# SCH_Hunter_2024-12-30.net
KiCad netlist of a schematic drawn in EasyEDA
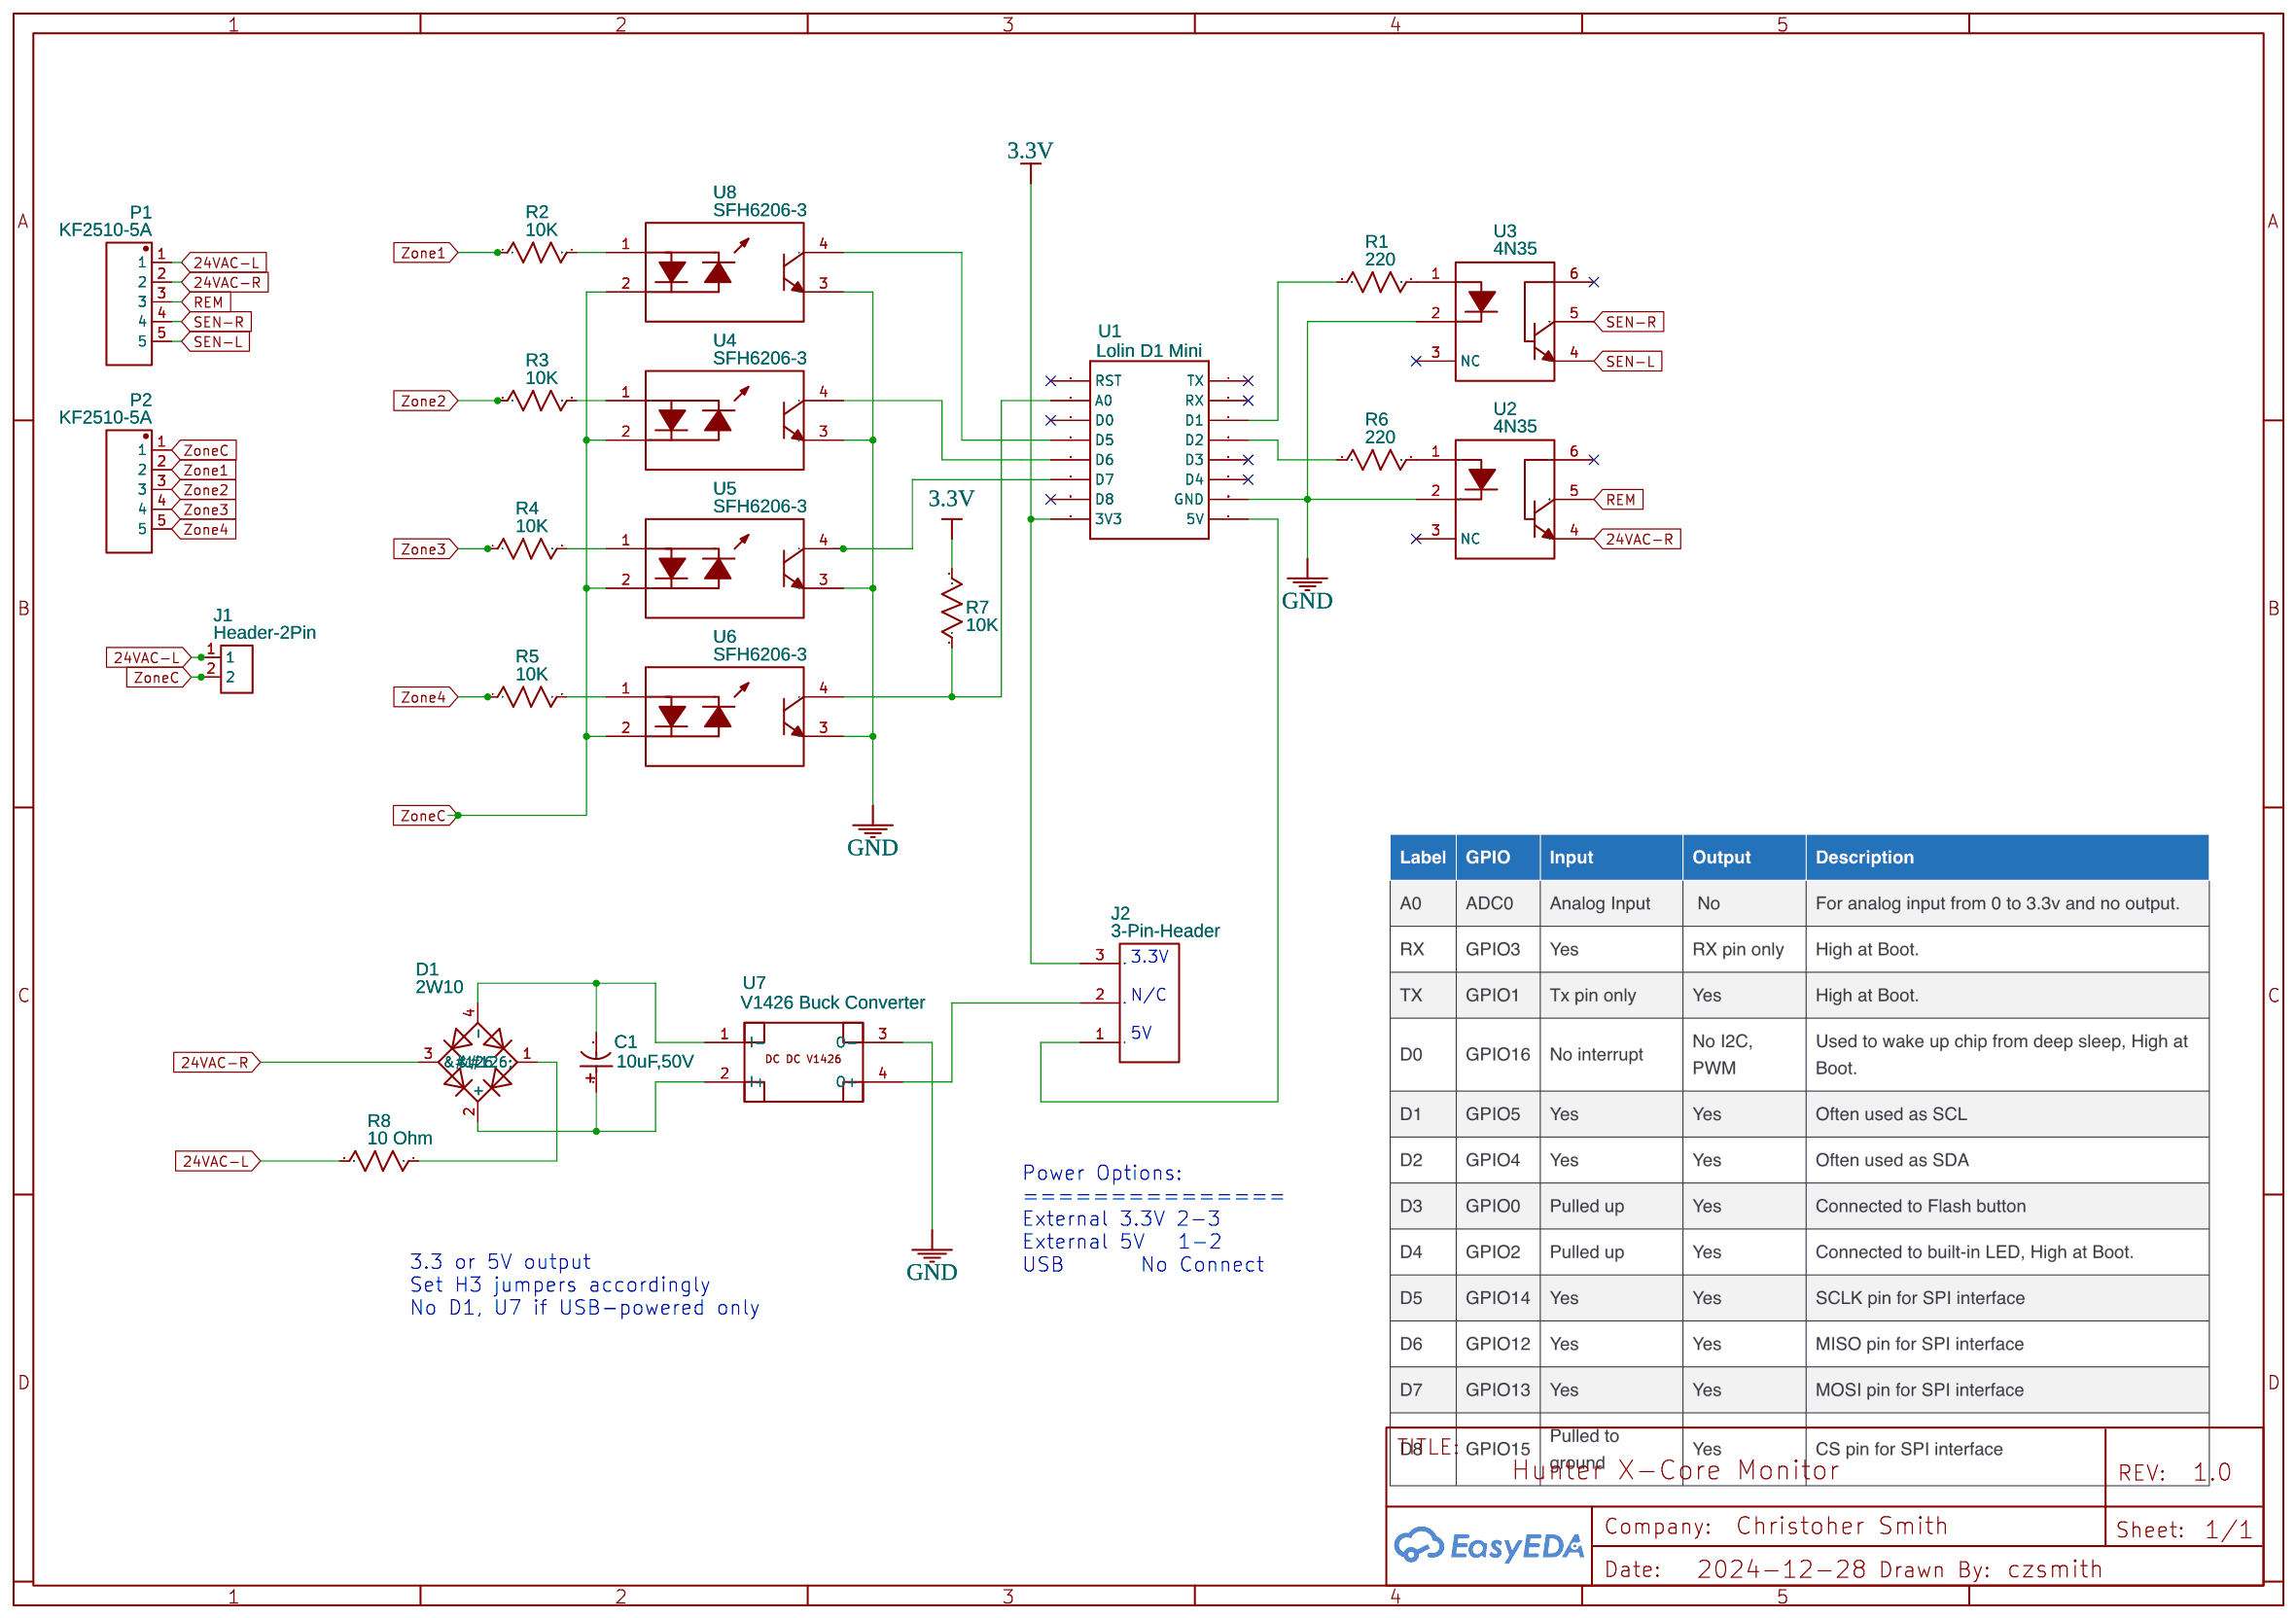
[diagram p0: schematic sheet]

(export (version "E")
  (design (tool "Eeschema 10.0.6"))
  (components
    (comp (ref "C1")
      (value "10uF,50V")
      (fields
        (field (name "Manufacturer Part") "KS475M050C07RR0VH2FP0")
        (field (name "Manufacturer") "CX(承兴)")
      )
      (libsource (lib "") (part "4.7uF 50V 4*7"))
    )
    (comp (ref "D1")
      (value "2W10")
      (fields (field (name "Manufacturer") "MDD"))
      (libsource (lib "") (part "2W10"))
    )
    (comp (ref "J1")
      (value "Header-2Pin")
      (fields
        (field (name "Manufacturer Part") "G800WC306018EU")
        (field (name "Manufacturer") "Amphenol ICC (Commercial Products)")
      )
      (libsource (lib "") (part "Header-2Pin"))
    )
    (comp (ref "J2") (value "3-Pin-Header") (libsource (lib "") (part "3-Pin-Header")))
    (comp (ref "P1")
      (value "KF2510-5A")
      (fields (field (name "Manufacturer Part") "2510-5A") (field (name "Manufacturer") "BOOMELE(博穆精密)"))
      (libsource (lib "") (part "KF2510-5A"))
    )
    (comp (ref "P2")
      (value "KF2510-5A")
      (fields (field (name "Manufacturer Part") "2510-5A") (field (name "Manufacturer") "BOOMELE(博穆精密)"))
      (libsource (lib "") (part "KF2510-5A"))
    )
    (comp (ref "R1") (value "220") (libsource (lib "") (part "R_0603_US")))
    (comp (ref "R2") (value "10K") (libsource (lib "") (part "R_0603_US")))
    (comp (ref "R3") (value "10K") (libsource (lib "") (part "R_0603_US")))
    (comp (ref "R4") (value "10K") (libsource (lib "") (part "R_0603_US")))
    (comp (ref "R5") (value "10K") (libsource (lib "") (part "R_0603_US")))
    (comp (ref "R6") (value "220") (libsource (lib "") (part "R_0603_US")))
    (comp (ref "R7") (value "10K") (libsource (lib "") (part "R_0603_US_2")))
    (comp (ref "R8") (value "10 Ohm") (libsource (lib "") (part "R_0603_US_1")))
    (comp (ref "U1") (value "Lolin D1 Mini") (libsource (lib "") (part "Lolin D1 Mini")))
    (comp (ref "U2")
      (value "4N35")
      (fields (field (name "Manufacturer Part") "LTV-4N35") (field (name "Manufacturer") "LITEON(光宝)"))
      (libsource (lib "") (part "LTV-4N35"))
    )
    (comp (ref "U3")
      (value "4N35")
      (fields (field (name "Manufacturer Part") "LTV-4N35") (field (name "Manufacturer") "LITEON(光宝)"))
      (libsource (lib "") (part "LTV-4N35"))
    )
    (comp (ref "U4")
      (value "SFH6206-3")
      (fields (field (name "Manufacturer") "VISHAY(威世)"))
      (libsource (lib "") (part "SFH6206-3"))
    )
    (comp (ref "U5")
      (value "SFH6206-3")
      (fields (field (name "Manufacturer") "VISHAY(威世)"))
      (libsource (lib "") (part "SFH6206-3"))
    )
    (comp (ref "U6")
      (value "SFH6206-3")
      (fields (field (name "Manufacturer") "VISHAY(威世)"))
      (libsource (lib "") (part "SFH6206-3"))
    )
    (comp (ref "U7")
      (value "V1426 Buck Converter")
      (libsource (lib "") (part "DC DC Buck Stepdown 5-30V {gt} 3.3V"))
    )
    (comp (ref "U8")
      (value "SFH6206-3")
      (fields (field (name "Manufacturer") "VISHAY(威世)"))
      (libsource (lib "") (part "SFH6206-3"))
    )
  )
  (nets
    (net (code "1") (name "3.3V") (class "Default")
      (node (ref "J2") (pin "3") (pinfunction "3_3") (pintype "unspecified"))
      (node (ref "R7") (pin "2") (pinfunction "2_2") (pintype "unspecified"))
      (node (ref "U1") (pin "3V3") (pinfunction "3V3_3V3") (pintype "unspecified"))
    )
    (net (code "2") (name "24VAC-L") (class "Default")
      (node (ref "J1") (pin "1") (pinfunction "1_1") (pintype "unspecified"))
      (node (ref "P1") (pin "1") (pinfunction "1_1") (pintype "unspecified"))
      (node (ref "R8") (pin "2") (pinfunction "2_2") (pintype "unspecified"))
    )
    (net (code "3") (name "24VAC-R") (class "Default")
      (node (ref "D1") (pin "3") (pinfunction "&#126;_3") (pintype "unspecified"))
      (node (ref "P1") (pin "2") (pinfunction "2_2") (pintype "unspecified"))
      (node (ref "U2") (pin "4") (pinfunction "4_4") (pintype "unspecified"))
    )
    (net (code "4") (name "GND") (class "Default")
      (node (ref "U1") (pin "GND") (pinfunction "GND_GND") (pintype "unspecified"))
      (node (ref "U2") (pin "2") (pinfunction "2_2") (pintype "unspecified"))
      (node (ref "U3") (pin "2") (pinfunction "2_2") (pintype "unspecified"))
      (node (ref "U4") (pin "3") (pinfunction "3_3") (pintype "unspecified"))
      (node (ref "U5") (pin "3") (pinfunction "3_3") (pintype "unspecified"))
      (node (ref "U6") (pin "3") (pinfunction "3_3") (pintype "unspecified"))
      (node (ref "U7") (pin "3") (pinfunction "O-_3") (pintype "unspecified"))
      (node (ref "U8") (pin "3") (pinfunction "3_3") (pintype "unspecified"))
    )
    (net (code "5") (name "Net-(D1-&#126;-Pad1)") (class "Default")
      (node (ref "D1") (pin "1") (pinfunction "&#126;_1") (pintype "unspecified"))
      (node (ref "R8") (pin "1") (pinfunction "1_1") (pintype "unspecified"))
    )
    (net (code "6") (name "Net-(D1-+)") (class "Default")
      (node (ref "C1") (pin "1") (pinfunction "1_1") (pintype "input"))
      (node (ref "D1") (pin "2") (pinfunction "+_2") (pintype "unspecified"))
      (node (ref "U7") (pin "2") (pinfunction "I+_2") (pintype "unspecified"))
    )
    (net (code "7") (name "Net-(D1--)") (class "Default")
      (node (ref "C1") (pin "2") (pinfunction "2_2") (pintype "input"))
      (node (ref "D1") (pin "4") (pinfunction "-_4") (pintype "unspecified"))
      (node (ref "U7") (pin "1") (pinfunction "I-_1") (pintype "unspecified"))
    )
    (net (code "8") (name "Net-(J2-Pad1)") (class "Default")
      (node (ref "J2") (pin "1") (pinfunction "1_1") (pintype "unspecified"))
      (node (ref "U1") (pin "5V") (pinfunction "5V_5V") (pintype "unspecified"))
    )
    (net (code "9") (name "Net-(R1-Pad1)") (class "Default")
      (node (ref "R1") (pin "1") (pinfunction "1_1") (pintype "unspecified"))
      (node (ref "U1") (pin "D1") (pinfunction "D1_D1") (pintype "unspecified"))
    )
    (net (code "10") (name "Net-(R1-Pad2)") (class "Default")
      (node (ref "R1") (pin "2") (pinfunction "2_2") (pintype "unspecified"))
      (node (ref "U3") (pin "1") (pinfunction "1_1") (pintype "unspecified"))
    )
    (net (code "11") (name "Net-(R2-Pad2)") (class "Default")
      (node (ref "R2") (pin "2") (pinfunction "2_2") (pintype "unspecified"))
      (node (ref "U8") (pin "1") (pinfunction "1_1") (pintype "unspecified"))
    )
    (net (code "12") (name "Net-(R3-Pad2)") (class "Default")
      (node (ref "R3") (pin "2") (pinfunction "2_2") (pintype "unspecified"))
      (node (ref "U4") (pin "1") (pinfunction "1_1") (pintype "unspecified"))
    )
    (net (code "13") (name "Net-(R4-Pad2)") (class "Default")
      (node (ref "R4") (pin "2") (pinfunction "2_2") (pintype "unspecified"))
      (node (ref "U5") (pin "1") (pinfunction "1_1") (pintype "unspecified"))
    )
    (net (code "14") (name "Net-(R5-Pad2)") (class "Default")
      (node (ref "R5") (pin "2") (pinfunction "2_2") (pintype "unspecified"))
      (node (ref "U6") (pin "1") (pinfunction "1_1") (pintype "unspecified"))
    )
    (net (code "15") (name "Net-(R6-Pad1)") (class "Default")
      (node (ref "R6") (pin "1") (pinfunction "1_1") (pintype "unspecified"))
      (node (ref "U1") (pin "D2") (pinfunction "D2_D2") (pintype "unspecified"))
    )
    (net (code "16") (name "Net-(R6-Pad2)") (class "Default")
      (node (ref "R6") (pin "2") (pinfunction "2_2") (pintype "unspecified"))
      (node (ref "U2") (pin "1") (pinfunction "1_1") (pintype "unspecified"))
    )
    (net (code "17") (name "Net-(R7-Pad1)") (class "Default")
      (node (ref "R7") (pin "1") (pinfunction "1_1") (pintype "unspecified"))
      (node (ref "U1") (pin "A0") (pinfunction "A0_A0") (pintype "unspecified"))
      (node (ref "U6") (pin "4") (pinfunction "4_4") (pintype "unspecified"))
    )
    (net (code "18") (name "Net-(U1-PadD5)") (class "Default")
      (node (ref "U1") (pin "D5") (pinfunction "D5_D5") (pintype "unspecified"))
      (node (ref "U8") (pin "4") (pinfunction "4_4") (pintype "unspecified"))
    )
    (net (code "19") (name "Net-(U1-PadD6)") (class "Default")
      (node (ref "U1") (pin "D6") (pinfunction "D6_D6") (pintype "unspecified"))
      (node (ref "U4") (pin "4") (pinfunction "4_4") (pintype "unspecified"))
    )
    (net (code "20") (name "Net-(U1-PadD7)") (class "Default")
      (node (ref "U1") (pin "D7") (pinfunction "D7_D7") (pintype "unspecified"))
      (node (ref "U5") (pin "4") (pinfunction "4_4") (pintype "unspecified"))
    )
    (net (code "21") (name "Net-(U7-O+)") (class "Default")
      (node (ref "J2") (pin "2") (pinfunction "2_2") (pintype "unspecified"))
      (node (ref "U7") (pin "4") (pinfunction "O+_4") (pintype "unspecified"))
    )
    (net (code "22") (name "REM") (class "Default")
      (node (ref "P1") (pin "3") (pinfunction "3_3") (pintype "unspecified"))
      (node (ref "U2") (pin "5") (pinfunction "5_5") (pintype "unspecified"))
    )
    (net (code "23") (name "SEN-L") (class "Default")
      (node (ref "P1") (pin "5") (pinfunction "5_5") (pintype "unspecified"))
      (node (ref "U3") (pin "4") (pinfunction "4_4") (pintype "unspecified"))
    )
    (net (code "24") (name "SEN-R") (class "Default")
      (node (ref "P1") (pin "4") (pinfunction "4_4") (pintype "unspecified"))
      (node (ref "U3") (pin "5") (pinfunction "5_5") (pintype "unspecified"))
    )
    (net (code "25") (name "Zone1") (class "Default")
      (node (ref "P2") (pin "2") (pinfunction "2_2") (pintype "unspecified"))
      (node (ref "R2") (pin "1") (pinfunction "1_1") (pintype "unspecified"))
    )
    (net (code "26") (name "Zone2") (class "Default")
      (node (ref "P2") (pin "3") (pinfunction "3_3") (pintype "unspecified"))
      (node (ref "R3") (pin "1") (pinfunction "1_1") (pintype "unspecified"))
    )
    (net (code "27") (name "Zone3") (class "Default")
      (node (ref "P2") (pin "4") (pinfunction "4_4") (pintype "unspecified"))
      (node (ref "R4") (pin "1") (pinfunction "1_1") (pintype "unspecified"))
    )
    (net (code "28") (name "Zone4") (class "Default")
      (node (ref "P2") (pin "5") (pinfunction "5_5") (pintype "unspecified"))
      (node (ref "R5") (pin "1") (pinfunction "1_1") (pintype "unspecified"))
    )
    (net (code "29") (name "ZoneC") (class "Default")
      (node (ref "J1") (pin "2") (pinfunction "2_2") (pintype "unspecified"))
      (node (ref "P2") (pin "1") (pinfunction "1_1") (pintype "unspecified"))
      (node (ref "U4") (pin "2") (pinfunction "2_2") (pintype "unspecified"))
      (node (ref "U5") (pin "2") (pinfunction "2_2") (pintype "unspecified"))
      (node (ref "U6") (pin "2") (pinfunction "2_2") (pintype "unspecified"))
      (node (ref "U8") (pin "2") (pinfunction "2_2") (pintype "unspecified"))
    )
    (net (code "30") (name "unconnected-(U1-PadD0)") (class "Default")
      (node (ref "U1") (pin "D0") (pinfunction "D0_D0") (pintype "unspecified+no_connect"))
    )
    (net (code "31") (name "unconnected-(U1-PadD3)") (class "Default")
      (node (ref "U1") (pin "D3") (pinfunction "D3_D3") (pintype "unspecified+no_connect"))
    )
    (net (code "32") (name "unconnected-(U1-PadD4)") (class "Default")
      (node (ref "U1") (pin "D4") (pinfunction "D4_D4") (pintype "unspecified+no_connect"))
    )
    (net (code "33") (name "unconnected-(U1-PadD8)") (class "Default")
      (node (ref "U1") (pin "D8") (pinfunction "D8_D8") (pintype "unspecified+no_connect"))
    )
    (net (code "34") (name "unconnected-(U1-PadRST)") (class "Default")
      (node (ref "U1") (pin "RST") (pinfunction "RST_RST") (pintype "unspecified+no_connect"))
    )
    (net (code "35") (name "unconnected-(U1-PadRX)") (class "Default")
      (node (ref "U1") (pin "RX") (pinfunction "RX_RX") (pintype "unspecified+no_connect"))
    )
    (net (code "36") (name "unconnected-(U1-PadTX)") (class "Default")
      (node (ref "U1") (pin "TX") (pinfunction "TX_TX") (pintype "unspecified+no_connect"))
    )
    (net (code "37") (name "unconnected-(U2-B-Pad6)") (class "Default")
      (node (ref "U2") (pin "6") (pinfunction "B_6") (pintype "unspecified+no_connect"))
    )
    (net (code "38") (name "unconnected-(U2-NC-Pad3)") (class "Default")
      (node (ref "U2") (pin "3") (pinfunction "NC_3") (pintype "unspecified+no_connect"))
    )
    (net (code "39") (name "unconnected-(U3-B-Pad6)") (class "Default")
      (node (ref "U3") (pin "6") (pinfunction "B_6") (pintype "unspecified+no_connect"))
    )
    (net (code "40") (name "unconnected-(U3-NC-Pad3)") (class "Default")
      (node (ref "U3") (pin "3") (pinfunction "NC_3") (pintype "unspecified+no_connect"))
    )
  )
)
